# NFC_Access_CPU2_R00.net
KiCad netlist of a schematic drawn in Altium Designer
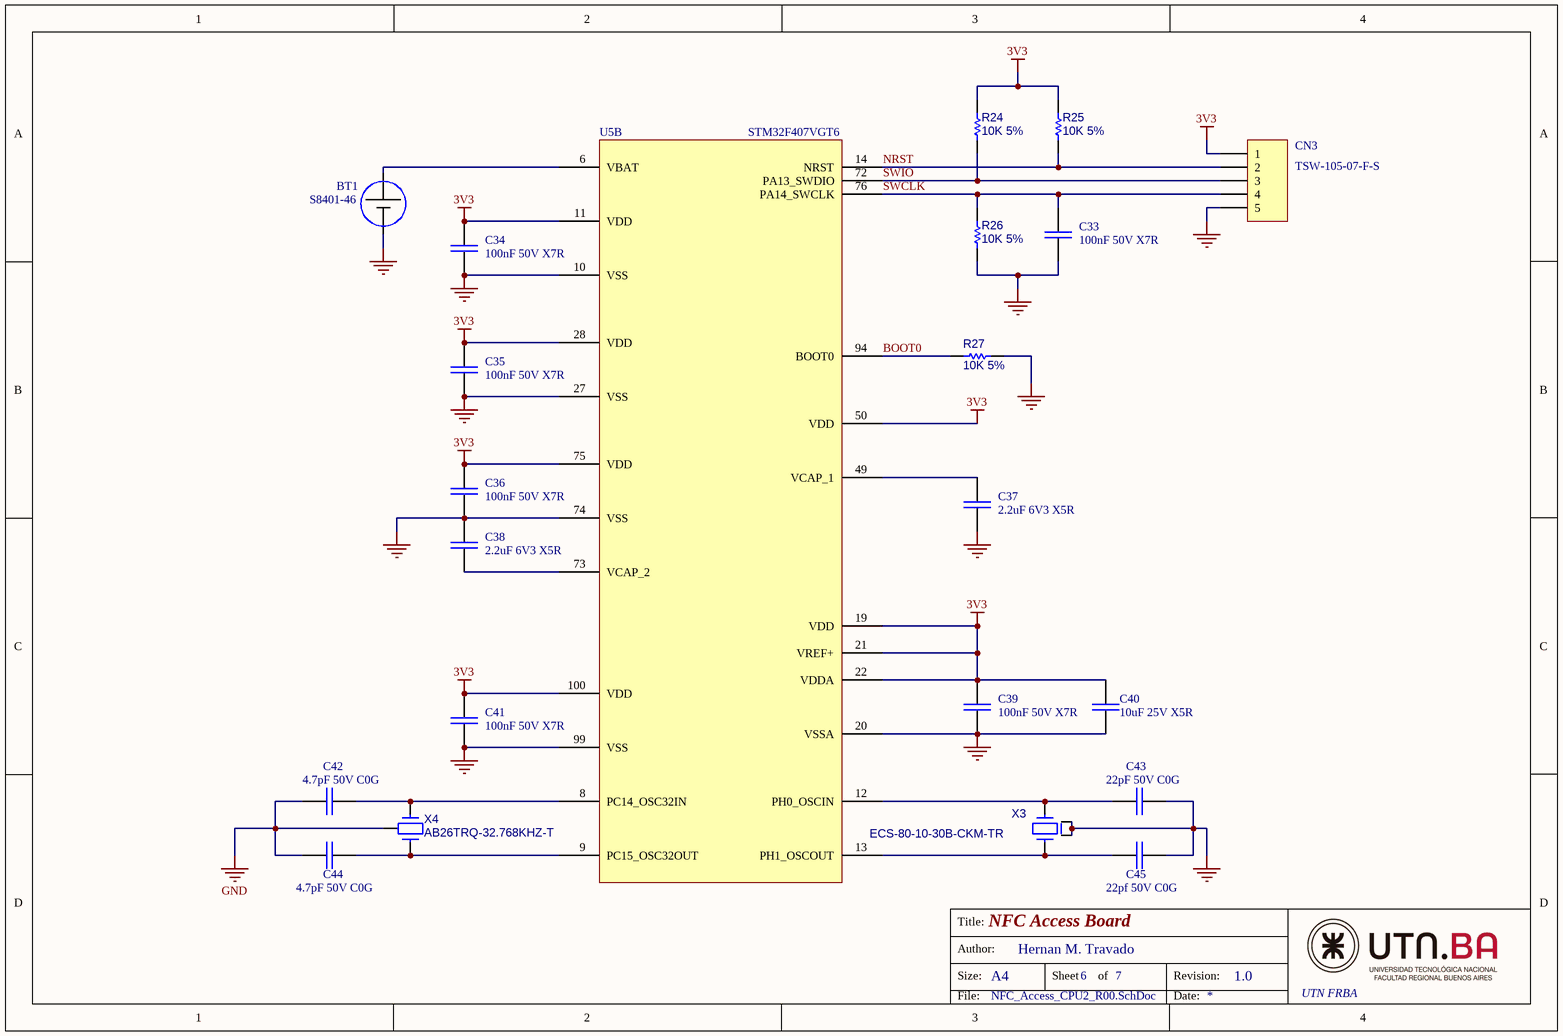
[diagram p0: NFC_Access_CPU2_R00.SchDoc]

(export (version "E")
  (design (tool "Eeschema 10.0.6"))
  (components
    (comp (ref "BT1")
      (value "S8401-46")
      (footprint "S8401-46")
      (description "BATT HLDR COIN 20MM 1 CEL PC PIN\r\n952-1743-2-ND")
      (libsource (lib "NFC_Access_Lib") (part "CR2032"))
    )
    (comp (ref "C33")
      (value "100nF 50V X7R")
      (footprint "C_0603")
      (description "Ceramic Capacitor\r\n1276-1018-2-ND")
      (libsource (lib "WiFiNode_R00") (part "Ceramic capacitor"))
    )
    (comp (ref "C34")
      (value "100nF 50V X7R")
      (footprint "C_0603")
      (description "Ceramic Capacitor\r\n1276-1018-2-ND")
      (libsource (lib "NFC_Access_Lib") (part "Ceramic capacitor"))
    )
    (comp (ref "C35")
      (value "100nF 50V X7R")
      (footprint "C_0603")
      (description "Ceramic Capacitor\r\n1276-1018-2-ND")
      (libsource (lib "NFC_Access_Lib") (part "Ceramic capacitor"))
    )
    (comp (ref "C36")
      (value "100nF 50V X7R")
      (footprint "C_0603")
      (description "Ceramic Capacitor\r\n1276-1018-2-ND")
      (libsource (lib "NFC_Access_Lib") (part "Ceramic capacitor"))
    )
    (comp (ref "C37")
      (value "2.2uF 6V3 X5R")
      (footprint "C_0603")
      (description "Ceramic Capacitor\r\n1276-1183-2-ND")
      (libsource (lib "NFC_Access_Lib") (part "Ceramic capacitor"))
    )
    (comp (ref "C38")
      (value "2.2uF 6V3 X5R")
      (footprint "C_0603")
      (description "Ceramic Capacitor\r\n1276-1183-2-ND")
      (libsource (lib "NFC_Access_Lib") (part "Ceramic capacitor"))
    )
    (comp (ref "C39")
      (value "100nF 50V X7R")
      (footprint "C_0603")
      (description "Ceramic Capacitor\r\n1276-1018-2-ND")
      (libsource (lib "NFC_Access_Lib") (part "Ceramic capacitor"))
    )
    (comp (ref "C40")
      (value "10uF 25V X5R")
      (footprint "C_0603")
      (description "Ceramic Capacitor\r\nMNF:GRM31CR61E106KA12L\r\nDGK:1276-1869-2-ND")
      (libsource (lib "WiFiNode_R00") (part "Ceramic capacitor"))
    )
    (comp (ref "C41")
      (value "100nF 50V X7R")
      (footprint "C_0603")
      (description "Ceramic Capacitor\r\n1276-1018-2-ND")
      (libsource (lib "NFC_Access_Lib") (part "Ceramic capacitor"))
    )
    (comp (ref "C42")
      (value "4.7pF 50V C0G")
      (footprint "C_0603")
      (description "Ceramic Capacitor\r\n1276-1792-2-ND")
      (libsource (lib "WiFiNode_R00") (part "Ceramic capacitor"))
    )
    (comp (ref "C43")
      (value "22pF 50V C0G")
      (footprint "C_0603")
      (description "Ceramic Capacitor\r\n1276-2228-2-ND")
      (libsource (lib "WiFiNode_R00") (part "Ceramic capacitor"))
    )
    (comp (ref "C44")
      (value "4.7pF 50V C0G")
      (footprint "C_0603")
      (description "Ceramic Capacitor\r\n1276-1792-2-ND")
      (libsource (lib "WiFiNode_R00") (part "Ceramic capacitor"))
    )
    (comp (ref "C45")
      (value "22pf 50V C0G")
      (footprint "C_0603")
      (description "Ceramic Capacitor\r\n1276-2228-2-ND")
      (libsource (lib "WiFiNode_R00") (part "Ceramic capacitor"))
    )
    (comp (ref "CN3")
      (value "TSW-105-07-F-S")
      (footprint "Header_M_1x5_0.1\"")
      (description "CONN HEADER VERT 5POS 2.54MM\r\nSAM10336-ND")
      (libsource (lib "WiFiNode_R00") (part "CONN_05P"))
    )
    (comp (ref "R24")
      (value "10K 5%")
      (footprint "R_0603")
      (description "Resistor\r\nCR0603-JW-103ELFTR-ND")
      (libsource (lib "WiFiNode_R00") (part "Res1"))
    )
    (comp (ref "R25")
      (value "10K 5%")
      (footprint "R_0603")
      (description "Resistor\r\nCR0603-JW-103ELFTR-ND")
      (libsource (lib "WiFiNode_R00") (part "Res1"))
    )
    (comp (ref "R26")
      (value "10K 5%")
      (footprint "R_0603")
      (description "Resistor\r\nCR0603-JW-103ELFTR-ND")
      (libsource (lib "WiFiNode_R00") (part "Res1"))
    )
    (comp (ref "R27")
      (value "10K 5%")
      (footprint "R_0603")
      (description "Resistor\r\nCR0603-JW-103ELFTR-ND")
      (libsource (lib "NFC_Access_Lib") (part "Res1"))
    )
    (comp (ref "U5")
      (value "STM32F407VGT6")
      (footprint "LQFP100")
      (description "Cortex M4 32bit CPU\r\n497-11605-ND")
      (libsource (lib "NFC_Access_Lib") (part "STM32F407"))
    )
    (comp (ref "X3")
      (value "ECS-80-10-30B-CKM-TR")
      (footprint "ABM3C")
      (description "Crystal 4 Vias + GND 8 MHz\r\n50-ECS-80-10-30B-CKM-TR-ND")
      (libsource (lib "WiFiNode_R00") (part "CRYSTAL_4P"))
    )
    (comp (ref "X4")
      (value "AB26TRQ-32.768KHZ-T")
      (footprint "AB26TQF")
      (description "Crystal 2 Vias + GND 32.768 kHz\r\n535-12051-2-ND")
      (libsource (lib "NFC_Access_Lib") (part "CRYSTAL 3P"))
    )
  )
  (nets
    (net (code "1") (name "/BOOT0") (class "Default")
      (node (ref "R27") (pin "2") (pinfunction "2_2") (pintype "passive"))
      (node (ref "U5") (pin "94") (pinfunction "BOOT0_94") (pintype "passive"))
    )
    (net (code "2") (name "/NRST") (class "Default")
      (node (ref "CN3") (pin "2") (pinfunction "2_2") (pintype "passive"))
      (node (ref "R25") (pin "2") (pinfunction "2_2") (pintype "passive"))
      (node (ref "U5") (pin "14") (pinfunction "NRST_14") (pintype "passive"))
    )
    (net (code "3") (name "/SWCLK") (class "Default")
      (node (ref "C33") (pin "1") (pinfunction "1_1") (pintype "passive"))
      (node (ref "CN3") (pin "4") (pinfunction "4_4") (pintype "passive"))
      (node (ref "R26") (pin "1") (pinfunction "1_1") (pintype "passive"))
      (node (ref "U5") (pin "76") (pinfunction "PA14_SWCLK_76") (pintype "passive"))
    )
    (net (code "4") (name "/SWIO") (class "Default")
      (node (ref "CN3") (pin "3") (pinfunction "3_3") (pintype "passive"))
      (node (ref "R24") (pin "2") (pinfunction "2_2") (pintype "passive"))
      (node (ref "U5") (pin "72") (pinfunction "PA13_SWDIO_72") (pintype "passive"))
    )
    (net (code "5") (name "3V3") (class "Default")
      (node (ref "C34") (pin "1") (pinfunction "1_1") (pintype "passive"))
      (node (ref "C35") (pin "1") (pinfunction "1_1") (pintype "passive"))
      (node (ref "C36") (pin "1") (pinfunction "1_1") (pintype "passive"))
      (node (ref "C39") (pin "2") (pinfunction "2_2") (pintype "passive"))
      (node (ref "C40") (pin "1") (pinfunction "1_1") (pintype "passive"))
      (node (ref "C41") (pin "1") (pinfunction "1_1") (pintype "passive"))
      (node (ref "CN3") (pin "1") (pinfunction "1_1") (pintype "passive"))
      (node (ref "R24") (pin "1") (pinfunction "1_1") (pintype "passive"))
      (node (ref "R25") (pin "1") (pinfunction "1_1") (pintype "passive"))
      (node (ref "U5") (pin "100") (pinfunction "VDD_100") (pintype "passive"))
      (node (ref "U5") (pin "11") (pinfunction "VDD_11") (pintype "passive"))
      (node (ref "U5") (pin "19") (pinfunction "VDD_19") (pintype "passive"))
      (node (ref "U5") (pin "21") (pinfunction "VREF+_21") (pintype "passive"))
      (node (ref "U5") (pin "22") (pinfunction "VDDA_22") (pintype "passive"))
      (node (ref "U5") (pin "28") (pinfunction "VDD_28") (pintype "passive"))
      (node (ref "U5") (pin "50") (pinfunction "VDD_50") (pintype "passive"))
      (node (ref "U5") (pin "75") (pinfunction "VDD_75") (pintype "passive"))
    )
    (net (code "6") (name "GND") (class "Default")
      (node (ref "BT1") (pin "1") (pinfunction "V-_1") (pintype "passive"))
      (node (ref "C33") (pin "2") (pinfunction "2_2") (pintype "passive"))
      (node (ref "C34") (pin "2") (pinfunction "2_2") (pintype "passive"))
      (node (ref "C35") (pin "2") (pinfunction "2_2") (pintype "passive"))
      (node (ref "C36") (pin "2") (pinfunction "2_2") (pintype "passive"))
      (node (ref "C37") (pin "2") (pinfunction "2_2") (pintype "passive"))
      (node (ref "C38") (pin "2") (pinfunction "2_2") (pintype "passive"))
      (node (ref "C39") (pin "1") (pinfunction "1_1") (pintype "passive"))
      (node (ref "C40") (pin "2") (pinfunction "2_2") (pintype "passive"))
      (node (ref "C41") (pin "2") (pinfunction "2_2") (pintype "passive"))
      (node (ref "C42") (pin "2") (pinfunction "2_2") (pintype "passive"))
      (node (ref "C43") (pin "2") (pinfunction "2_2") (pintype "passive"))
      (node (ref "C44") (pin "2") (pinfunction "2_2") (pintype "passive"))
      (node (ref "C45") (pin "2") (pinfunction "2_2") (pintype "passive"))
      (node (ref "CN3") (pin "5") (pinfunction "5_5") (pintype "passive"))
      (node (ref "R26") (pin "2") (pinfunction "2_2") (pintype "passive"))
      (node (ref "R27") (pin "1") (pinfunction "1_1") (pintype "passive"))
      (node (ref "U5") (pin "10") (pinfunction "VSS_10") (pintype "passive"))
      (node (ref "U5") (pin "20") (pinfunction "VSSA_20") (pintype "passive"))
      (node (ref "U5") (pin "27") (pinfunction "VSS_27") (pintype "passive"))
      (node (ref "U5") (pin "74") (pinfunction "VSS_74") (pintype "passive"))
      (node (ref "U5") (pin "99") (pinfunction "VSS_99") (pintype "passive"))
      (node (ref "X3") (pin "2") (pinfunction "2_2") (pintype "passive"))
      (node (ref "X3") (pin "4") (pinfunction "4_4") (pintype "passive"))
      (node (ref "X4") (pin "3") (pinfunction "3_3") (pintype "passive"))
    )
    (net (code "7") (name "Net-(BT1-V+)") (class "Default")
      (node (ref "BT1") (pin "2") (pinfunction "V+_2") (pintype "passive"))
      (node (ref "U5") (pin "6") (pinfunction "VBAT_6") (pintype "passive"))
    )
    (net (code "8") (name "Net-(U5B-PC14_OSC32IN)") (class "Default")
      (node (ref "C42") (pin "1") (pinfunction "1_1") (pintype "passive"))
      (node (ref "U5") (pin "8") (pinfunction "PC14_OSC32IN_8") (pintype "passive"))
      (node (ref "X4") (pin "2") (pinfunction "2_2") (pintype "passive"))
    )
    (net (code "9") (name "Net-(U5B-PC15_OSC32OUT)") (class "Default")
      (node (ref "C44") (pin "1") (pinfunction "1_1") (pintype "passive"))
      (node (ref "U5") (pin "9") (pinfunction "PC15_OSC32OUT_9") (pintype "passive"))
      (node (ref "X4") (pin "1") (pinfunction "1_1") (pintype "passive"))
    )
    (net (code "10") (name "Net-(U5B-PH0_OSCIN)") (class "Default")
      (node (ref "C43") (pin "1") (pinfunction "1_1") (pintype "passive"))
      (node (ref "U5") (pin "12") (pinfunction "PH0_OSCIN_12") (pintype "passive"))
      (node (ref "X3") (pin "1") (pinfunction "1_1") (pintype "passive"))
    )
    (net (code "11") (name "Net-(U5B-PH1_OSCOUT)") (class "Default")
      (node (ref "C45") (pin "1") (pinfunction "1_1") (pintype "passive"))
      (node (ref "U5") (pin "13") (pinfunction "PH1_OSCOUT_13") (pintype "passive"))
      (node (ref "X3") (pin "3") (pinfunction "3_3") (pintype "passive"))
    )
    (net (code "12") (name "Net-(U5B-VCAP_1)") (class "Default")
      (node (ref "C37") (pin "1") (pinfunction "1_1") (pintype "passive"))
      (node (ref "U5") (pin "49") (pinfunction "VCAP_1_49") (pintype "passive"))
    )
    (net (code "13") (name "Net-(U5B-VCAP_2)") (class "Default")
      (node (ref "C38") (pin "1") (pinfunction "1_1") (pintype "passive"))
      (node (ref "U5") (pin "73") (pinfunction "VCAP_2_73") (pintype "passive"))
    )
  )
)
